# Peripherals.net
KiCad netlist of a schematic drawn in Altium Designer
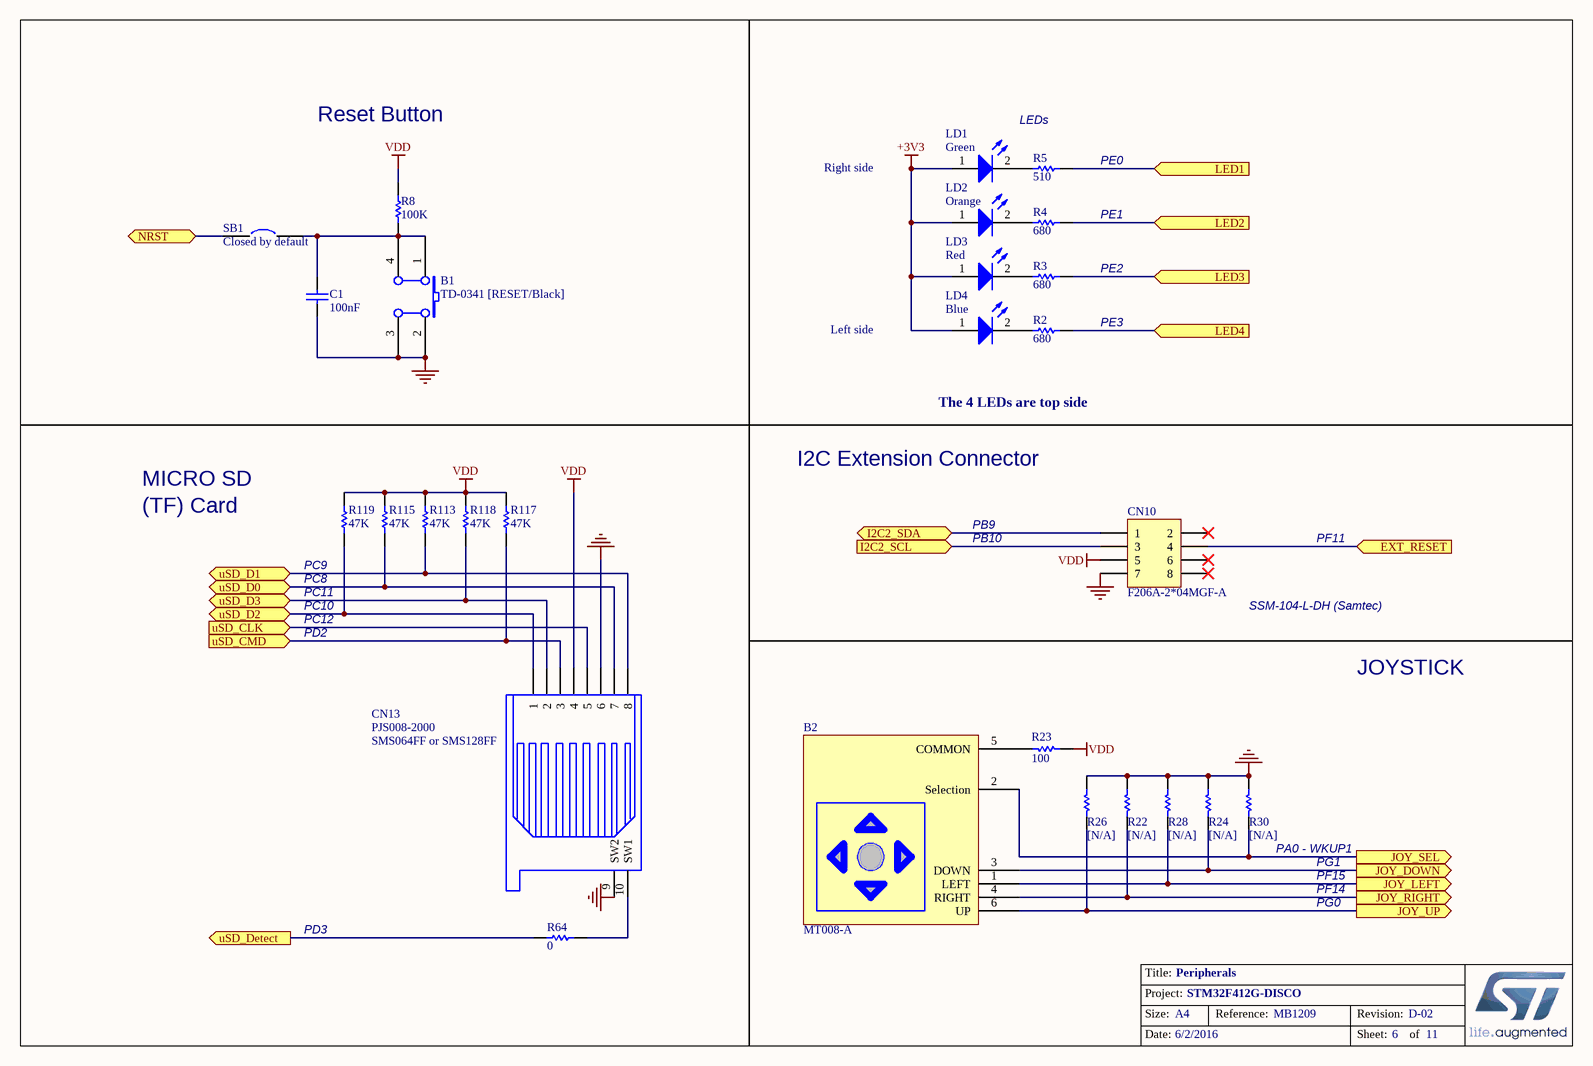
[diagram p0: Peripherals.SchDoc]

(export (version "E")
  (design (tool "Eeschema 10.0.6"))
  (components
    (comp (ref "B1")
      (value "TD-0341 [RESET/Black]")
      (footprint "PB10")
      (description "SE PUSHBUTTON")
      (libsource (lib "Documents") (part "SW PUSHBUTTON"))
    )
    (comp (ref "B2")
      (value "MT008-A")
      (footprint "MT-008A")
      (description "Joystick")
      (libsource (lib "MB1209_2") (part "MT-008A"))
    )
    (comp (ref "C1")
      (value "100nF")
      (footprint "0402C")
      (description "Capacitor")
      (fields (field (name "PUBLISHER") "Altium Limited"))
      (libsource (lib "Miscellaneous Devices") (part "CAP"))
    )
    (comp (ref "CN10")
      (value "F206A-2*04MGF-A")
      (footprint "SSM-104-L-DH")
      (description "Header, 5-Pin, Dual row")
      (fields (field (name "PUBLISHER") "Altium Limited"))
      (libsource (lib "mb1045") (part "SSM-104-L-DH"))
    )
    (comp (ref "CN13")
      (value "PJS008-2000")
      (footprint "MSD_PJS008_")
      (libsource (lib "MB525") (part "SMS016AFA5E"))
    )
    (comp (ref "LD1")
      (value "Green")
      (footprint "0603D")
      (description "Typical RED, GREEN, YELLOW, AMBER GaAs LED")
      (fields (field (name "PUBLISHER") "Altium Limited"))
      (libsource (lib "Miscellaneous Devices") (part "LED2"))
    )
    (comp (ref "LD2")
      (value "Orange")
      (footprint "0603D")
      (description "Typical RED, GREEN, YELLOW, AMBER GaAs LED")
      (fields (field (name "PUBLISHER") "Altium Limited"))
      (libsource (lib "Miscellaneous Devices") (part "LED2"))
    )
    (comp (ref "LD3")
      (value "Red")
      (footprint "0603D")
      (description "Typical RED, GREEN, YELLOW, AMBER GaAs LED")
      (fields (field (name "PUBLISHER") "Altium Limited"))
      (libsource (lib "Miscellaneous Devices") (part "LED2"))
    )
    (comp (ref "LD4")
      (value "Blue")
      (footprint "0603D")
      (description "Typical RED, GREEN, YELLOW, AMBER GaAs LED")
      (fields (field (name "PUBLISHER") "Altium Limited"))
      (libsource (lib "Miscellaneous Devices") (part "LED2"))
    )
    (comp (ref "R2")
      (value "680")
      (footprint "0402R")
      (description "Resistor")
      (fields (field (name "PUBLISHER") "Altium Limited"))
      (libsource (lib "Miscellaneous Devices") (part "Res1"))
    )
    (comp (ref "R3")
      (value "680")
      (footprint "0402R")
      (description "Resistor")
      (fields (field (name "PUBLISHER") "Altium Limited"))
      (libsource (lib "Miscellaneous Devices") (part "Res1"))
    )
    (comp (ref "R4")
      (value "680")
      (footprint "0402R")
      (description "Resistor")
      (fields (field (name "PUBLISHER") "Altium Limited"))
      (libsource (lib "Miscellaneous Devices") (part "Res1"))
    )
    (comp (ref "R5")
      (value "510")
      (footprint "0603R")
      (description "Resistor")
      (fields (field (name "PUBLISHER") "Altium Limited"))
      (libsource (lib "Miscellaneous Devices") (part "Res1"))
    )
    (comp (ref "R8")
      (value "100K")
      (footprint "0402R")
      (description "Resistor")
      (fields (field (name "PUBLISHER") "Altium Limited"))
      (libsource (lib "Miscellaneous Devices") (part "res1"))
    )
    (comp (ref "R22")
      (value "[N/A]")
      (footprint "0402R")
      (description "Resistor")
      (fields (field (name "PUBLISHER") "Altium Limited"))
      (libsource (lib "Miscellaneous Devices") (part "Res1"))
    )
    (comp (ref "R23")
      (value "100")
      (footprint "0402R")
      (description "Resistor")
      (fields (field (name "PUBLISHER") "Altium Limited"))
      (libsource (lib "Miscellaneous Devices") (part "Res1"))
    )
    (comp (ref "R24")
      (value "[N/A]")
      (footprint "0402R")
      (description "Resistor")
      (fields (field (name "PUBLISHER") "Altium Limited"))
      (libsource (lib "Miscellaneous Devices") (part "Res1"))
    )
    (comp (ref "R26")
      (value "[N/A]")
      (footprint "0402R")
      (description "Resistor")
      (fields (field (name "PUBLISHER") "Altium Limited"))
      (libsource (lib "Miscellaneous Devices") (part "Res1"))
    )
    (comp (ref "R28")
      (value "[N/A]")
      (footprint "0402R")
      (description "Resistor")
      (fields (field (name "PUBLISHER") "Altium Limited"))
      (libsource (lib "Miscellaneous Devices") (part "Res1"))
    )
    (comp (ref "R30")
      (value "[N/A]")
      (footprint "0402R")
      (description "Resistor")
      (fields (field (name "PUBLISHER") "Altium Limited"))
      (libsource (lib "Miscellaneous Devices") (part "Res1"))
    )
    (comp (ref "R64")
      (value "0")
      (footprint "SB_0603")
      (description "Resistor")
      (fields (field (name "PUBLISHER") "Altium Limited"))
      (libsource (lib "Miscellaneous Devices") (part "Res1"))
    )
    (comp (ref "R113")
      (value "47K")
      (footprint "0402R")
      (description "Resistor")
      (fields (field (name "PUBLISHER") "Altium Limited"))
      (libsource (lib "Miscellaneous Devices") (part "res1"))
    )
    (comp (ref "R115")
      (value "47K")
      (footprint "0402R")
      (description "Resistor")
      (fields (field (name "PUBLISHER") "Altium Limited"))
      (libsource (lib "Miscellaneous Devices") (part "res1"))
    )
    (comp (ref "R117")
      (value "47K")
      (footprint "0402R")
      (description "Resistor")
      (fields (field (name "PUBLISHER") "Altium Limited"))
      (libsource (lib "Miscellaneous Devices") (part "res1"))
    )
    (comp (ref "R118")
      (value "47K")
      (footprint "0402R")
      (description "Resistor")
      (fields (field (name "PUBLISHER") "Altium Limited"))
      (libsource (lib "Miscellaneous Devices") (part "res1"))
    )
    (comp (ref "R119")
      (value "47K")
      (footprint "0402R")
      (description "Resistor")
      (fields (field (name "PUBLISHER") "Altium Limited"))
      (libsource (lib "Miscellaneous Devices") (part "res1"))
    )
    (comp (ref "SB1")
      (value "Closed by default")
      (footprint "SB_0603")
      (description "Circuit Breaker")
      (fields (field (name "PUBLISHER") "Altium Limited"))
      (libsource (lib "Miscellaneous Devices") (part "Circuit Breaker"))
    )
  )
  (nets
    (net (code "1") (name "+3V3") (class "Default")
      (node (ref "LD1") (pin "1") (pinfunction "A_1") (pintype "passive"))
      (node (ref "LD2") (pin "1") (pinfunction "A_1") (pintype "passive"))
      (node (ref "LD3") (pin "1") (pinfunction "A_1") (pintype "passive"))
      (node (ref "LD4") (pin "1") (pinfunction "A_1") (pintype "passive"))
    )
    (net (code "2") (name "/EXT_RESET") (class "Default")
      (node (ref "CN10") (pin "4") (pinfunction "4_4") (pintype "passive"))
    )
    (net (code "3") (name "/I2C2_SCL") (class "Default")
      (node (ref "CN10") (pin "3") (pinfunction "3_3") (pintype "passive"))
    )
    (net (code "4") (name "/I2C2_SDA") (class "Default")
      (node (ref "CN10") (pin "1") (pinfunction "1_1") (pintype "passive"))
    )
    (net (code "5") (name "/JOY_DOWN") (class "Default")
      (node (ref "B2") (pin "3") (pinfunction "DOWN_3") (pintype "passive"))
      (node (ref "R24") (pin "1") (pinfunction "1_1") (pintype "passive"))
    )
    (net (code "6") (name "/JOY_LEFT") (class "Default")
      (node (ref "B2") (pin "1") (pinfunction "LEFT_1") (pintype "passive"))
      (node (ref "R28") (pin "1") (pinfunction "1_1") (pintype "passive"))
    )
    (net (code "7") (name "/JOY_RIGHT") (class "Default")
      (node (ref "B2") (pin "4") (pinfunction "RIGHT_4") (pintype "passive"))
      (node (ref "R22") (pin "1") (pinfunction "1_1") (pintype "passive"))
    )
    (net (code "8") (name "/JOY_SEL") (class "Default")
      (node (ref "B2") (pin "2") (pinfunction "Selection_2") (pintype "passive"))
      (node (ref "R30") (pin "2") (pinfunction "2_2") (pintype "passive"))
    )
    (net (code "9") (name "/JOY_UP") (class "Default")
      (node (ref "B2") (pin "6") (pinfunction "UP_6") (pintype "passive"))
      (node (ref "R26") (pin "1") (pinfunction "1_1") (pintype "passive"))
    )
    (net (code "10") (name "/LED1") (class "Default")
      (node (ref "R5") (pin "1") (pinfunction "1_1") (pintype "passive"))
    )
    (net (code "11") (name "/LED2") (class "Default")
      (node (ref "R4") (pin "1") (pinfunction "1_1") (pintype "passive"))
    )
    (net (code "12") (name "/LED3") (class "Default")
      (node (ref "R3") (pin "1") (pinfunction "1_1") (pintype "passive"))
    )
    (net (code "13") (name "/LED4") (class "Default")
      (node (ref "R2") (pin "1") (pinfunction "1_1") (pintype "passive"))
    )
    (net (code "14") (name "/NRST") (class "Default")
      (node (ref "SB1") (pin "1") (pinfunction "1_1") (pintype "passive"))
    )
    (net (code "15") (name "/uSD_CLK") (class "Default")
      (node (ref "CN13") (pin "5") (pinfunction "5_5") (pintype "passive"))
    )
    (net (code "16") (name "/uSD_CMD") (class "Default")
      (node (ref "CN13") (pin "3") (pinfunction "3_3") (pintype "passive"))
      (node (ref "R117") (pin "2") (pinfunction "2_2") (pintype "passive"))
    )
    (net (code "17") (name "/uSD_D0") (class "Default")
      (node (ref "CN13") (pin "7") (pinfunction "7_7") (pintype "passive"))
      (node (ref "R115") (pin "2") (pinfunction "2_2") (pintype "passive"))
    )
    (net (code "18") (name "/uSD_D1") (class "Default")
      (node (ref "CN13") (pin "8") (pinfunction "8_8") (pintype "passive"))
      (node (ref "R113") (pin "2") (pinfunction "2_2") (pintype "passive"))
    )
    (net (code "19") (name "/uSD_D2") (class "Default")
      (node (ref "CN13") (pin "1") (pinfunction "1_1") (pintype "passive"))
      (node (ref "R119") (pin "2") (pinfunction "2_2") (pintype "passive"))
    )
    (net (code "20") (name "/uSD_D3") (class "Default")
      (node (ref "CN13") (pin "2") (pinfunction "2_2") (pintype "passive"))
      (node (ref "R118") (pin "2") (pinfunction "2_2") (pintype "passive"))
    )
    (net (code "21") (name "/uSD_Detect") (class "Default")
      (node (ref "R64") (pin "1") (pinfunction "1_1") (pintype "passive"))
    )
    (net (code "22") (name "GND") (class "Default")
      (node (ref "B1") (pin "2") (pinfunction "B0_2") (pintype "passive"))
      (node (ref "B1") (pin "3") (pinfunction "B1_3") (pintype "passive"))
      (node (ref "C1") (pin "1") (pinfunction "1_1") (pintype "passive"))
      (node (ref "CN10") (pin "7") (pinfunction "7_7") (pintype "passive"))
      (node (ref "CN13") (pin "6") (pinfunction "6_6") (pintype "passive"))
      (node (ref "CN13") (pin "9") (pinfunction "SW2_9") (pintype "passive"))
      (node (ref "R22") (pin "2") (pinfunction "2_2") (pintype "passive"))
      (node (ref "R24") (pin "2") (pinfunction "2_2") (pintype "passive"))
      (node (ref "R26") (pin "2") (pinfunction "2_2") (pintype "passive"))
      (node (ref "R28") (pin "2") (pinfunction "2_2") (pintype "passive"))
      (node (ref "R30") (pin "1") (pinfunction "1_1") (pintype "passive"))
    )
    (net (code "23") (name "Net-(B1-A0)") (class "Default")
      (node (ref "B1") (pin "1") (pinfunction "A0_1") (pintype "passive"))
      (node (ref "B1") (pin "4") (pinfunction "A1_4") (pintype "passive"))
      (node (ref "C1") (pin "2") (pinfunction "2_2") (pintype "passive"))
      (node (ref "R8") (pin "2") (pinfunction "2_2") (pintype "passive"))
      (node (ref "SB1") (pin "2") (pinfunction "2_2") (pintype "passive"))
    )
    (net (code "24") (name "Net-(B2-COMMON)") (class "Default")
      (node (ref "B2") (pin "5") (pinfunction "COMMON_5") (pintype "passive"))
      (node (ref "R23") (pin "2") (pinfunction "2_2") (pintype "passive"))
    )
    (net (code "25") (name "Net-(CN13-SW1)") (class "Default")
      (node (ref "CN13") (pin "10") (pinfunction "SW1_10") (pintype "passive"))
      (node (ref "R64") (pin "2") (pinfunction "2_2") (pintype "passive"))
    )
    (net (code "26") (name "Net-(LD1-K)") (class "Default")
      (node (ref "LD1") (pin "2") (pinfunction "K_2") (pintype "passive"))
      (node (ref "R5") (pin "2") (pinfunction "2_2") (pintype "passive"))
    )
    (net (code "27") (name "Net-(LD2-K)") (class "Default")
      (node (ref "LD2") (pin "2") (pinfunction "K_2") (pintype "passive"))
      (node (ref "R4") (pin "2") (pinfunction "2_2") (pintype "passive"))
    )
    (net (code "28") (name "Net-(LD3-K)") (class "Default")
      (node (ref "LD3") (pin "2") (pinfunction "K_2") (pintype "passive"))
      (node (ref "R3") (pin "2") (pinfunction "2_2") (pintype "passive"))
    )
    (net (code "29") (name "Net-(LD4-K)") (class "Default")
      (node (ref "LD4") (pin "2") (pinfunction "K_2") (pintype "passive"))
      (node (ref "R2") (pin "2") (pinfunction "2_2") (pintype "passive"))
    )
    (net (code "30") (name "VDD") (class "Default")
      (node (ref "CN10") (pin "5") (pinfunction "5_5") (pintype "passive"))
      (node (ref "CN13") (pin "4") (pinfunction "4_4") (pintype "passive"))
      (node (ref "R113") (pin "1") (pinfunction "1_1") (pintype "passive"))
      (node (ref "R115") (pin "1") (pinfunction "1_1") (pintype "passive"))
      (node (ref "R117") (pin "1") (pinfunction "1_1") (pintype "passive"))
      (node (ref "R118") (pin "1") (pinfunction "1_1") (pintype "passive"))
      (node (ref "R119") (pin "1") (pinfunction "1_1") (pintype "passive"))
      (node (ref "R23") (pin "1") (pinfunction "1_1") (pintype "passive"))
      (node (ref "R8") (pin "1") (pinfunction "1_1") (pintype "passive"))
    )
    (net (code "31") (name "unconnected-(CN10-Pad2)") (class "Default")
      (node (ref "CN10") (pin "2") (pinfunction "2_2") (pintype "passive+no_connect"))
    )
    (net (code "32") (name "unconnected-(CN10-Pad6)") (class "Default")
      (node (ref "CN10") (pin "6") (pinfunction "6_6") (pintype "passive+no_connect"))
    )
    (net (code "33") (name "unconnected-(CN10-Pad8)") (class "Default")
      (node (ref "CN10") (pin "8") (pinfunction "8_8") (pintype "passive+no_connect"))
    )
  )
)
